# OmapSystem.net
KiCad netlist of a schematic drawn in Altium Designer
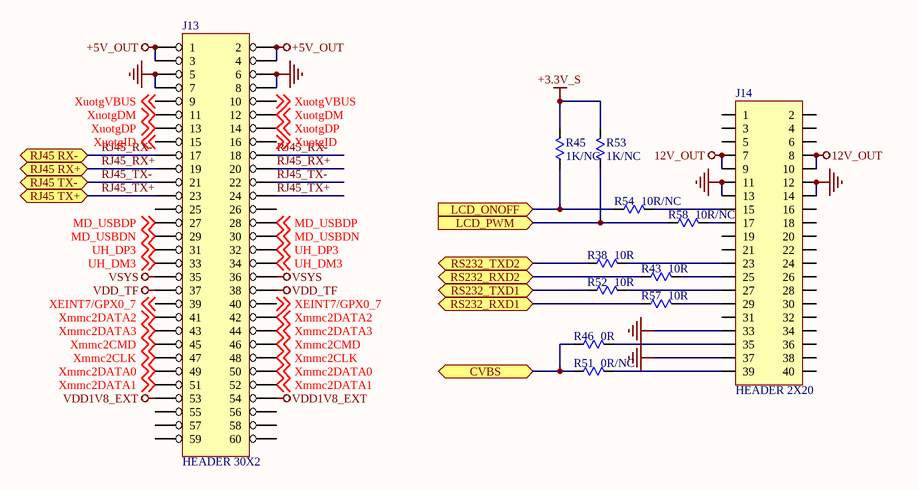
[diagram p0: OmapSystem.SchDoc]

(export (version "E")
  (design (tool "Eeschema 10.0.6"))
  (components
    (comp (ref "J13")
      (value "HEADER 30X2")
      (footprint "HD2X30-2.00")
      (libsource (lib "Connector Class") (part "HEADER 30X2"))
    )
    (comp (ref "J14")
      (value "HEADER 2X20")
      (footprint "HD2X20-2.00")
      (libsource (lib "Connector Class") (part "HEADER 2X20"))
    )
    (comp (ref "R38")
      (value "10R")
      (footprint "R0805")
      (description "Resistor")
      (fields (field (name "PUBLISHER") "Altium Limited"))
      (libsource (lib "UP-Robot") (part "Res"))
    )
    (comp (ref "R43")
      (value "10R")
      (footprint "R0805")
      (description "Resistor")
      (fields (field (name "PUBLISHER") "Altium Limited"))
      (libsource (lib "UP-Robot") (part "Res"))
    )
    (comp (ref "R45")
      (value "1K/NC")
      (footprint "R0805")
      (description "Resistor")
      (fields (field (name "PUBLISHER") "Altium Limited"))
      (libsource (lib "UP-Robot") (part "Res"))
    )
    (comp (ref "R46")
      (value "0R")
      (footprint "R0805")
      (description "Resistor")
      (fields (field (name "PUBLISHER") "Altium Limited"))
      (libsource (lib "UP-Robot") (part "Res"))
    )
    (comp (ref "R51")
      (value "0R/NC")
      (footprint "R0805")
      (description "Resistor")
      (fields (field (name "PUBLISHER") "Altium Limited"))
      (libsource (lib "UP-Robot") (part "Res"))
    )
    (comp (ref "R52")
      (value "10R")
      (footprint "R0805")
      (description "Resistor")
      (fields (field (name "PUBLISHER") "Altium Limited"))
      (libsource (lib "UP-Robot") (part "Res"))
    )
    (comp (ref "R53")
      (value "1K/NC")
      (footprint "R0805")
      (description "Resistor")
      (fields (field (name "PUBLISHER") "Altium Limited"))
      (libsource (lib "UP-Robot") (part "Res"))
    )
    (comp (ref "R54")
      (value "10R/NC")
      (footprint "R0805")
      (description "Resistor")
      (fields (field (name "PUBLISHER") "Altium Limited"))
      (libsource (lib "UP-Robot") (part "Res"))
    )
    (comp (ref "R57")
      (value "10R")
      (footprint "R0805")
      (description "Resistor")
      (fields (field (name "PUBLISHER") "Altium Limited"))
      (libsource (lib "UP-Robot") (part "Res"))
    )
    (comp (ref "R58")
      (value "10R/NC")
      (footprint "R0805")
      (description "Resistor")
      (fields (field (name "PUBLISHER") "Altium Limited"))
      (libsource (lib "UP-Robot") (part "Res"))
    )
  )
  (nets
    (net (code "1") (name "+3.3V_S") (class "Default")
      (node (ref "R45") (pin "1") (pinfunction "1_1") (pintype "passive"))
      (node (ref "R53") (pin "1") (pinfunction "1_1") (pintype "passive"))
    )
    (net (code "2") (name "+5V_OUT") (class "Default")
      (node (ref "J13") (pin "1") (pinfunction "1_1") (pintype "passive"))
      (node (ref "J13") (pin "2") (pinfunction "2_2") (pintype "passive"))
      (node (ref "J13") (pin "3") (pinfunction "3_3") (pintype "passive"))
      (node (ref "J13") (pin "4") (pinfunction "4_4") (pintype "passive"))
    )
    (net (code "3") (name "/CVBS") (class "Default")
      (node (ref "R46") (pin "2") (pinfunction "2_2") (pintype "passive"))
      (node (ref "R51") (pin "2") (pinfunction "2_2") (pintype "passive"))
    )
    (net (code "4") (name "/LCD_ONOFF") (class "Default")
      (node (ref "R45") (pin "2") (pinfunction "2_2") (pintype "passive"))
      (node (ref "R54") (pin "2") (pinfunction "2_2") (pintype "passive"))
    )
    (net (code "5") (name "/LCD_PWM") (class "Default")
      (node (ref "R53") (pin "2") (pinfunction "2_2") (pintype "passive"))
      (node (ref "R58") (pin "2") (pinfunction "2_2") (pintype "passive"))
    )
    (net (code "6") (name "/RJ45_RX+") (class "Default")
      (node (ref "J13") (pin "19") (pinfunction "19_19") (pintype "passive"))
      (node (ref "J13") (pin "20") (pinfunction "20_20") (pintype "passive"))
    )
    (net (code "7") (name "/RJ45_RX-") (class "Default")
      (node (ref "J13") (pin "17") (pinfunction "17_17") (pintype "passive"))
      (node (ref "J13") (pin "18") (pinfunction "18_18") (pintype "passive"))
    )
    (net (code "8") (name "/RJ45_TX+") (class "Default")
      (node (ref "J13") (pin "23") (pinfunction "23_23") (pintype "passive"))
      (node (ref "J13") (pin "24") (pinfunction "24_24") (pintype "passive"))
    )
    (net (code "9") (name "/RJ45_TX-") (class "Default")
      (node (ref "J13") (pin "21") (pinfunction "21_21") (pintype "passive"))
      (node (ref "J13") (pin "22") (pinfunction "22_22") (pintype "passive"))
    )
    (net (code "10") (name "/RS232_RXD1") (class "Default")
      (node (ref "R57") (pin "2") (pinfunction "2_2") (pintype "passive"))
    )
    (net (code "11") (name "/RS232_RXD2") (class "Default")
      (node (ref "R43") (pin "2") (pinfunction "2_2") (pintype "passive"))
    )
    (net (code "12") (name "/RS232_TXD1") (class "Default")
      (node (ref "R52") (pin "2") (pinfunction "2_2") (pintype "passive"))
    )
    (net (code "13") (name "/RS232_TXD2") (class "Default")
      (node (ref "R38") (pin "2") (pinfunction "2_2") (pintype "passive"))
    )
    (net (code "14") (name "12V_OUT") (class "Default")
      (node (ref "J14") (pin "10") (pinfunction "10_10") (pintype "passive"))
      (node (ref "J14") (pin "7") (pinfunction "7_7") (pintype "passive"))
      (node (ref "J14") (pin "8") (pinfunction "8_8") (pintype "passive"))
      (node (ref "J14") (pin "9") (pinfunction "9_9") (pintype "passive"))
    )
    (net (code "15") (name "MD_USBDN") (class "Default")
      (node (ref "J13") (pin "29") (pinfunction "29_29") (pintype "passive"))
      (node (ref "J13") (pin "30") (pinfunction "30_30") (pintype "passive"))
    )
    (net (code "16") (name "MD_USBDP") (class "Default")
      (node (ref "J13") (pin "27") (pinfunction "27_27") (pintype "passive"))
      (node (ref "J13") (pin "28") (pinfunction "28_28") (pintype "passive"))
    )
    (net (code "17") (name "Net-(J14-Pad15)") (class "Default")
      (node (ref "J14") (pin "15") (pinfunction "15_15") (pintype "passive"))
      (node (ref "R54") (pin "1") (pinfunction "1_1") (pintype "passive"))
    )
    (net (code "18") (name "Net-(J14-Pad17)") (class "Default")
      (node (ref "J14") (pin "17") (pinfunction "17_17") (pintype "passive"))
      (node (ref "R58") (pin "1") (pinfunction "1_1") (pintype "passive"))
    )
    (net (code "19") (name "Net-(J14-Pad23)") (class "Default")
      (node (ref "J14") (pin "23") (pinfunction "23_23") (pintype "passive"))
      (node (ref "R38") (pin "1") (pinfunction "1_1") (pintype "passive"))
    )
    (net (code "20") (name "Net-(J14-Pad25)") (class "Default")
      (node (ref "J14") (pin "25") (pinfunction "25_25") (pintype "passive"))
      (node (ref "R43") (pin "1") (pinfunction "1_1") (pintype "passive"))
    )
    (net (code "21") (name "Net-(J14-Pad27)") (class "Default")
      (node (ref "J14") (pin "27") (pinfunction "27_27") (pintype "passive"))
      (node (ref "R52") (pin "1") (pinfunction "1_1") (pintype "passive"))
    )
    (net (code "22") (name "Net-(J14-Pad29)") (class "Default")
      (node (ref "J14") (pin "29") (pinfunction "29_29") (pintype "passive"))
      (node (ref "R57") (pin "1") (pinfunction "1_1") (pintype "passive"))
    )
    (net (code "23") (name "Net-(J14-Pad35)") (class "Default")
      (node (ref "J14") (pin "35") (pinfunction "35_35") (pintype "passive"))
      (node (ref "R46") (pin "1") (pinfunction "1_1") (pintype "passive"))
    )
    (net (code "24") (name "Net-(J14-Pad39)") (class "Default")
      (node (ref "J14") (pin "39") (pinfunction "39_39") (pintype "passive"))
      (node (ref "R51") (pin "1") (pinfunction "1_1") (pintype "passive"))
    )
    (net (code "25") (name "SGND") (class "Default")
      (node (ref "J13") (pin "5") (pinfunction "5_5") (pintype "passive"))
      (node (ref "J13") (pin "6") (pinfunction "6_6") (pintype "passive"))
      (node (ref "J13") (pin "7") (pinfunction "7_7") (pintype "passive"))
      (node (ref "J13") (pin "8") (pinfunction "8_8") (pintype "passive"))
      (node (ref "J14") (pin "11") (pinfunction "11_11") (pintype "passive"))
      (node (ref "J14") (pin "12") (pinfunction "12_12") (pintype "passive"))
      (node (ref "J14") (pin "13") (pinfunction "13_13") (pintype "passive"))
      (node (ref "J14") (pin "14") (pinfunction "14_14") (pintype "passive"))
      (node (ref "J14") (pin "33") (pinfunction "33_33") (pintype "passive"))
      (node (ref "J14") (pin "37") (pinfunction "37_37") (pintype "passive"))
    )
    (net (code "26") (name "UH_DM3") (class "Default")
      (node (ref "J13") (pin "33") (pinfunction "33_33") (pintype "passive"))
      (node (ref "J13") (pin "34") (pinfunction "34_34") (pintype "passive"))
    )
    (net (code "27") (name "UH_DP3") (class "Default")
      (node (ref "J13") (pin "31") (pinfunction "31_31") (pintype "passive"))
      (node (ref "J13") (pin "32") (pinfunction "32_32") (pintype "passive"))
    )
    (net (code "28") (name "VDD1V8_EXT") (class "Default")
      (node (ref "J13") (pin "53") (pinfunction "53_53") (pintype "passive"))
      (node (ref "J13") (pin "54") (pinfunction "54_54") (pintype "passive"))
    )
    (net (code "29") (name "VDD_TF") (class "Default")
      (node (ref "J13") (pin "37") (pinfunction "37_37") (pintype "passive"))
      (node (ref "J13") (pin "38") (pinfunction "38_38") (pintype "passive"))
    )
    (net (code "30") (name "VSYS") (class "Default")
      (node (ref "J13") (pin "35") (pinfunction "35_35") (pintype "passive"))
      (node (ref "J13") (pin "36") (pinfunction "36_36") (pintype "passive"))
    )
    (net (code "31") (name "XEINT7{slash}GPX0_7") (class "Default")
      (node (ref "J13") (pin "39") (pinfunction "39_39") (pintype "passive"))
      (node (ref "J13") (pin "40") (pinfunction "40_40") (pintype "passive"))
    )
    (net (code "32") (name "Xmmc2CLK") (class "Default")
      (node (ref "J13") (pin "47") (pinfunction "47_47") (pintype "passive"))
      (node (ref "J13") (pin "48") (pinfunction "48_48") (pintype "passive"))
    )
    (net (code "33") (name "Xmmc2CMD") (class "Default")
      (node (ref "J13") (pin "45") (pinfunction "45_45") (pintype "passive"))
      (node (ref "J13") (pin "46") (pinfunction "46_46") (pintype "passive"))
    )
    (net (code "34") (name "Xmmc2DATA0") (class "Default")
      (node (ref "J13") (pin "49") (pinfunction "49_49") (pintype "passive"))
      (node (ref "J13") (pin "50") (pinfunction "50_50") (pintype "passive"))
    )
    (net (code "35") (name "Xmmc2DATA1") (class "Default")
      (node (ref "J13") (pin "51") (pinfunction "51_51") (pintype "passive"))
      (node (ref "J13") (pin "52") (pinfunction "52_52") (pintype "passive"))
    )
    (net (code "36") (name "Xmmc2DATA2") (class "Default")
      (node (ref "J13") (pin "41") (pinfunction "41_41") (pintype "passive"))
      (node (ref "J13") (pin "42") (pinfunction "42_42") (pintype "passive"))
    )
    (net (code "37") (name "Xmmc2DATA3") (class "Default")
      (node (ref "J13") (pin "43") (pinfunction "43_43") (pintype "passive"))
      (node (ref "J13") (pin "44") (pinfunction "44_44") (pintype "passive"))
    )
    (net (code "38") (name "XuotgDM") (class "Default")
      (node (ref "J13") (pin "11") (pinfunction "11_11") (pintype "passive"))
      (node (ref "J13") (pin "12") (pinfunction "12_12") (pintype "passive"))
    )
    (net (code "39") (name "XuotgDP") (class "Default")
      (node (ref "J13") (pin "13") (pinfunction "13_13") (pintype "passive"))
      (node (ref "J13") (pin "14") (pinfunction "14_14") (pintype "passive"))
    )
    (net (code "40") (name "XuotgID") (class "Default")
      (node (ref "J13") (pin "15") (pinfunction "15_15") (pintype "passive"))
      (node (ref "J13") (pin "16") (pinfunction "16_16") (pintype "passive"))
    )
    (net (code "41") (name "XuotgVBUS") (class "Default")
      (node (ref "J13") (pin "10") (pinfunction "10_10") (pintype "passive"))
      (node (ref "J13") (pin "9") (pinfunction "9_9") (pintype "passive"))
    )
    (net (code "42") (name "unconnected-(J13-Pad25)") (class "Default")
      (node (ref "J13") (pin "25") (pinfunction "25_25") (pintype "passive"))
    )
    (net (code "43") (name "unconnected-(J13-Pad26)") (class "Default")
      (node (ref "J13") (pin "26") (pinfunction "26_26") (pintype "passive"))
    )
    (net (code "44") (name "unconnected-(J13-Pad55)") (class "Default")
      (node (ref "J13") (pin "55") (pinfunction "55_55") (pintype "passive"))
    )
    (net (code "45") (name "unconnected-(J13-Pad56)") (class "Default")
      (node (ref "J13") (pin "56") (pinfunction "56_56") (pintype "passive"))
    )
    (net (code "46") (name "unconnected-(J13-Pad57)") (class "Default")
      (node (ref "J13") (pin "57") (pinfunction "57_57") (pintype "passive"))
    )
    (net (code "47") (name "unconnected-(J13-Pad58)") (class "Default")
      (node (ref "J13") (pin "58") (pinfunction "58_58") (pintype "passive"))
    )
    (net (code "48") (name "unconnected-(J13-Pad59)") (class "Default")
      (node (ref "J13") (pin "59") (pinfunction "59_59") (pintype "passive"))
    )
    (net (code "49") (name "unconnected-(J13-Pad60)") (class "Default")
      (node (ref "J13") (pin "60") (pinfunction "60_60") (pintype "passive"))
    )
    (net (code "50") (name "unconnected-(J14-Pad1)") (class "Default")
      (node (ref "J14") (pin "1") (pinfunction "1_1") (pintype "passive"))
    )
    (net (code "51") (name "unconnected-(J14-Pad2)") (class "Default")
      (node (ref "J14") (pin "2") (pinfunction "2_2") (pintype "passive"))
    )
    (net (code "52") (name "unconnected-(J14-Pad3)") (class "Default")
      (node (ref "J14") (pin "3") (pinfunction "3_3") (pintype "passive"))
    )
    (net (code "53") (name "unconnected-(J14-Pad4)") (class "Default")
      (node (ref "J14") (pin "4") (pinfunction "4_4") (pintype "passive"))
    )
    (net (code "54") (name "unconnected-(J14-Pad5)") (class "Default")
      (node (ref "J14") (pin "5") (pinfunction "5_5") (pintype "passive"))
    )
    (net (code "55") (name "unconnected-(J14-Pad6)") (class "Default")
      (node (ref "J14") (pin "6") (pinfunction "6_6") (pintype "passive"))
    )
    (net (code "56") (name "unconnected-(J14-Pad16)") (class "Default")
      (node (ref "J14") (pin "16") (pinfunction "16_16") (pintype "passive"))
    )
    (net (code "57") (name "unconnected-(J14-Pad18)") (class "Default")
      (node (ref "J14") (pin "18") (pinfunction "18_18") (pintype "passive"))
    )
    (net (code "58") (name "unconnected-(J14-Pad19)") (class "Default")
      (node (ref "J14") (pin "19") (pinfunction "19_19") (pintype "passive"))
    )
    (net (code "59") (name "unconnected-(J14-Pad20)") (class "Default")
      (node (ref "J14") (pin "20") (pinfunction "20_20") (pintype "passive"))
    )
    (net (code "60") (name "unconnected-(J14-Pad21)") (class "Default")
      (node (ref "J14") (pin "21") (pinfunction "21_21") (pintype "passive"))
    )
    (net (code "61") (name "unconnected-(J14-Pad22)") (class "Default")
      (node (ref "J14") (pin "22") (pinfunction "22_22") (pintype "passive"))
    )
    (net (code "62") (name "unconnected-(J14-Pad24)") (class "Default")
      (node (ref "J14") (pin "24") (pinfunction "24_24") (pintype "passive"))
    )
    (net (code "63") (name "unconnected-(J14-Pad26)") (class "Default")
      (node (ref "J14") (pin "26") (pinfunction "26_26") (pintype "passive"))
    )
    (net (code "64") (name "unconnected-(J14-Pad28)") (class "Default")
      (node (ref "J14") (pin "28") (pinfunction "28_28") (pintype "passive"))
    )
    (net (code "65") (name "unconnected-(J14-Pad30)") (class "Default")
      (node (ref "J14") (pin "30") (pinfunction "30_30") (pintype "passive"))
    )
    (net (code "66") (name "unconnected-(J14-Pad31)") (class "Default")
      (node (ref "J14") (pin "31") (pinfunction "31_31") (pintype "passive"))
    )
    (net (code "67") (name "unconnected-(J14-Pad32)") (class "Default")
      (node (ref "J14") (pin "32") (pinfunction "32_32") (pintype "passive"))
    )
    (net (code "68") (name "unconnected-(J14-Pad34)") (class "Default")
      (node (ref "J14") (pin "34") (pinfunction "34_34") (pintype "passive"))
    )
    (net (code "69") (name "unconnected-(J14-Pad36)") (class "Default")
      (node (ref "J14") (pin "36") (pinfunction "36_36") (pintype "passive"))
    )
    (net (code "70") (name "unconnected-(J14-Pad38)") (class "Default")
      (node (ref "J14") (pin "38") (pinfunction "38_38") (pintype "passive"))
    )
    (net (code "71") (name "unconnected-(J14-Pad40)") (class "Default")
      (node (ref "J14") (pin "40") (pinfunction "40_40") (pintype "passive"))
    )
  )
)
